# echo.net
KiCad netlist of a schematic drawn in EAGLE
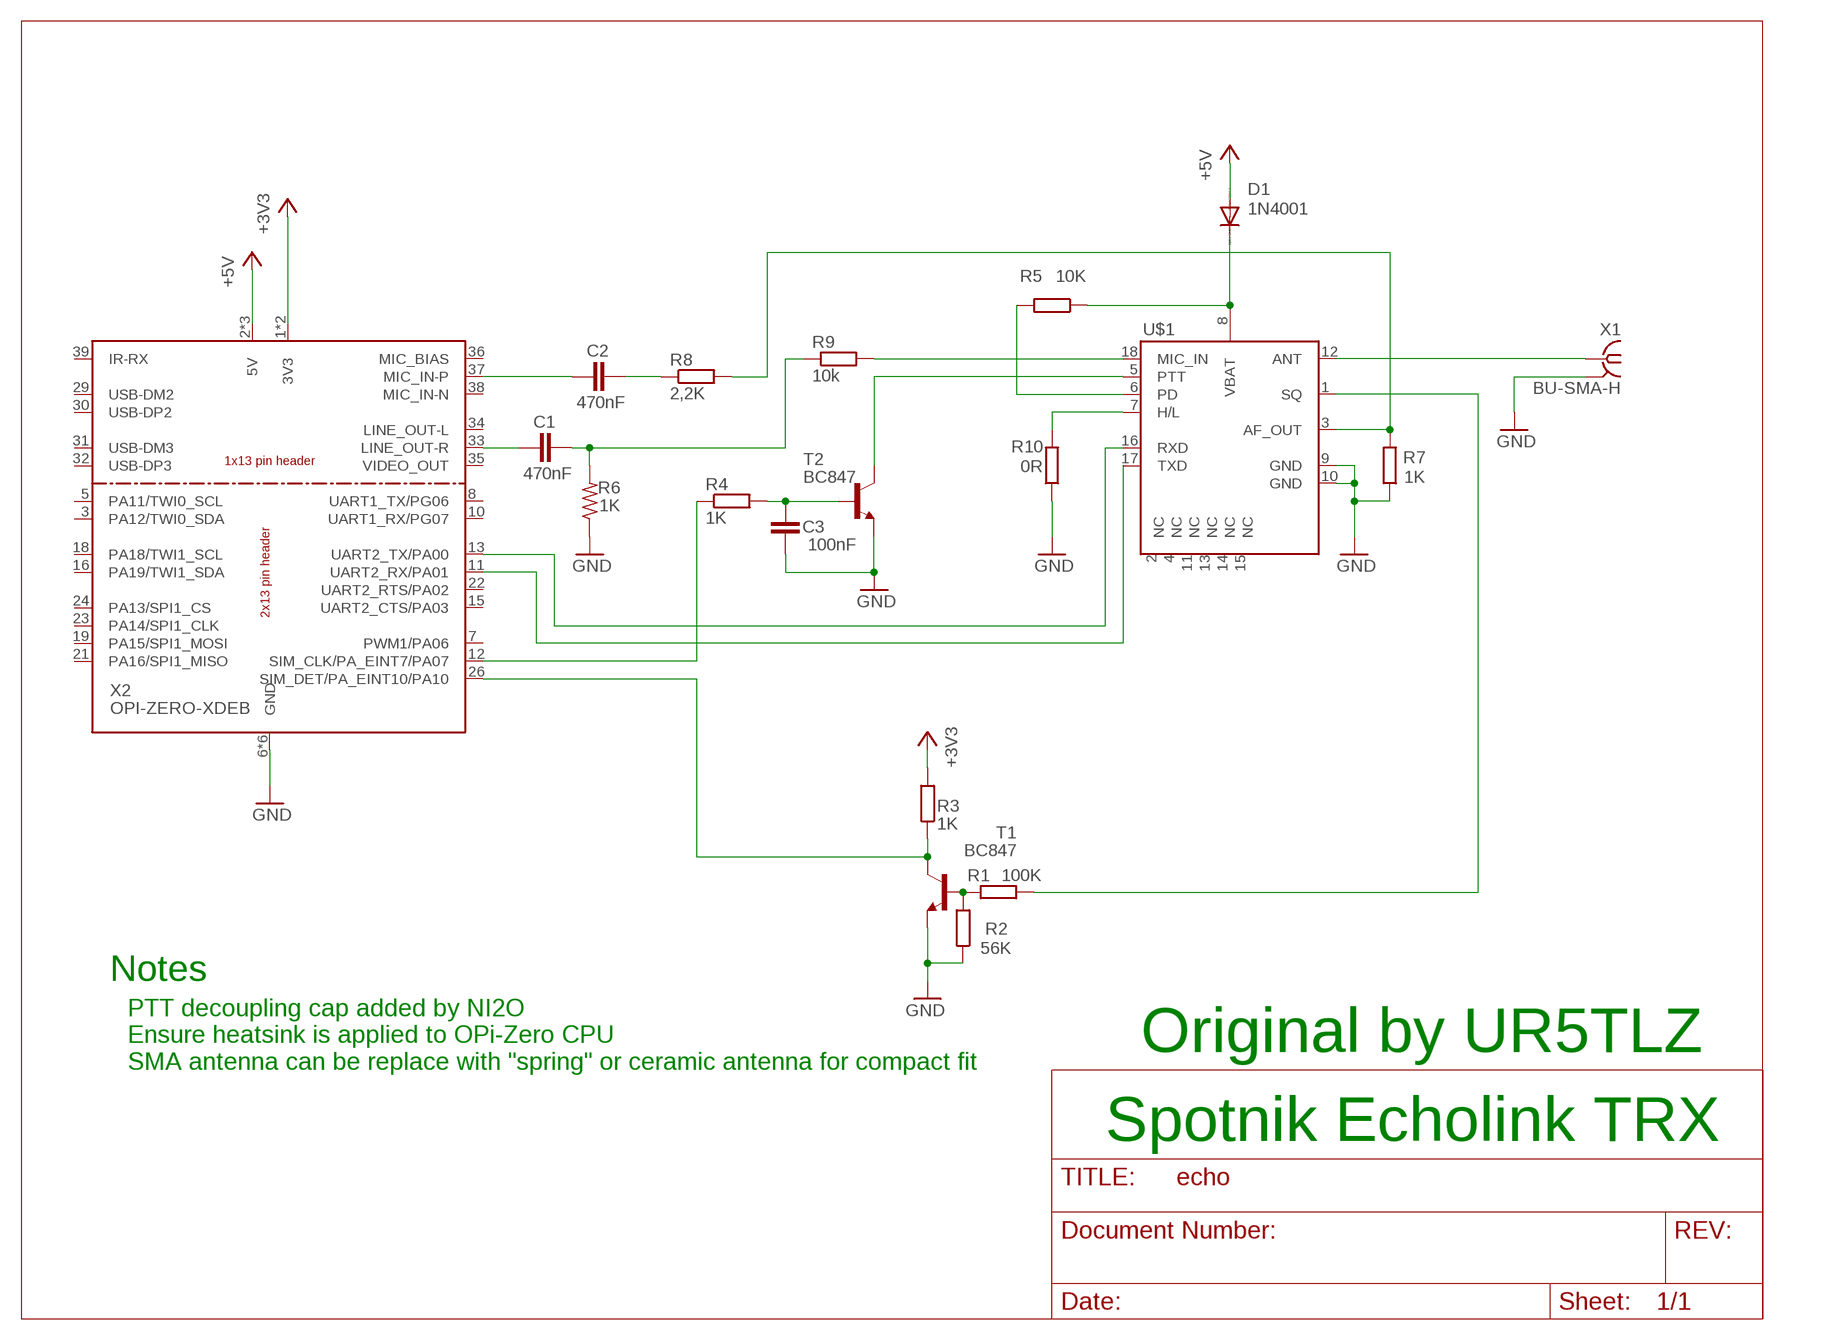
[diagram p0: schematic, sheet 1]

(export (version "E")
  (design (tool "Eeschema 10.0.6"))
  (components
    (comp (ref "C1")
      (value "470nF")
      (footprint "eagle-import:C0805")
      (libsource (lib "eagle-import") (part "C-EUC0805"))
    )
    (comp (ref "C2")
      (value "470nF")
      (footprint "eagle-import:C0805")
      (libsource (lib "eagle-import") (part "C-EUC0805"))
    )
    (comp (ref "C3")
      (value "100nF")
      (footprint "eagle-import:C0805")
      (libsource (lib "eagle-import") (part "C-EUC0805"))
    )
    (comp (ref "D1")
      (value "1N4001")
      (footprint "eagle-import:DO41-10")
      (libsource (lib "eagle-import") (part "DIODE-DO41-10"))
    )
    (comp (ref "R1")
      (value "100K")
      (footprint "eagle-import:R0805")
      (libsource (lib "eagle-import") (part "R-EU_R0805"))
    )
    (comp (ref "R2")
      (value "56K")
      (footprint "eagle-import:R0805")
      (libsource (lib "eagle-import") (part "R-EU_R0805"))
    )
    (comp (ref "R3")
      (value "1K")
      (footprint "eagle-import:R0805")
      (libsource (lib "eagle-import") (part "R-EU_R0805"))
    )
    (comp (ref "R4")
      (value "1K")
      (footprint "eagle-import:R0805")
      (libsource (lib "eagle-import") (part "R-EU_R0805"))
    )
    (comp (ref "R5")
      (value "10K")
      (footprint "eagle-import:R0805")
      (libsource (lib "eagle-import") (part "R-EU_R0805"))
    )
    (comp (ref "R6")
      (value "1K")
      (footprint "eagle-import:R0805")
      (libsource (lib "eagle-import") (part "R-US_R0805"))
    )
    (comp (ref "R7")
      (value "1K")
      (footprint "eagle-import:R0805")
      (libsource (lib "eagle-import") (part "R-EU_R0805"))
    )
    (comp (ref "R8")
      (value "2,2K")
      (footprint "eagle-import:R0805")
      (libsource (lib "eagle-import") (part "R-EU_R0805"))
    )
    (comp (ref "R9")
      (value "10k")
      (footprint "eagle-import:R0805")
      (libsource (lib "eagle-import") (part "R-EU_R0805"))
    )
    (comp (ref "R10")
      (value "0R")
      (footprint "eagle-import:R0805")
      (libsource (lib "eagle-import") (part "R-EU_R0805"))
    )
    (comp (ref "T1")
      (value "BC847")
      (footprint "eagle-import:SOT23")
      (libsource (lib "eagle-import") (part "BC847"))
    )
    (comp (ref "T2")
      (value "BC847")
      (footprint "eagle-import:SOT23")
      (libsource (lib "eagle-import") (part "BC847"))
    )
    (comp (ref "U$1")
      (value "DRA818A")
      (footprint "eagle-import:DRA818A")
      (libsource (lib "eagle-import") (part "DRA818A"))
    )
    (comp (ref "X1")
      (value "BU-SMA-H")
      (footprint "eagle-import:BU-SMA-H")
      (libsource (lib "eagle-import") (part "BU-SMA-H"))
    )
    (comp (ref "X2")
      (value "OPI-ZERO-XDEB")
      (footprint "eagle-import:OPIOHATDEB")
      (libsource (lib "eagle-import") (part "OPI-ZERO-XDEB"))
    )
  )
  (nets
    (net (code "1") (name "+3V3") (class "Default")
      (node (ref "R3") (pin "2") (pinfunction "2_2") (pintype "passive"))
      (node (ref "X2") (pin "1") (pinfunction "3V3_1") (pintype "power_in"))
      (node (ref "X2") (pin "17") (pinfunction "3V3_17") (pintype "power_in"))
    )
    (net (code "2") (name "+5V") (class "Default")
      (node (ref "D1") (pin "A") (pinfunction "A_A") (pintype "passive"))
      (node (ref "X2") (pin "2") (pinfunction "5V_2") (pintype "power_in"))
      (node (ref "X2") (pin "27") (pinfunction "5V_27") (pintype "power_in"))
      (node (ref "X2") (pin "4") (pinfunction "5V_4") (pintype "power_in"))
    )
    (net (code "3") (name "GND") (class "Default")
      (node (ref "C3") (pin "2") (pinfunction "2_2") (pintype "passive"))
      (node (ref "R10") (pin "1") (pinfunction "1_1") (pintype "passive"))
      (node (ref "R2") (pin "1") (pinfunction "1_1") (pintype "passive"))
      (node (ref "R6") (pin "1") (pinfunction "1_1") (pintype "passive"))
      (node (ref "R7") (pin "1") (pinfunction "1_1") (pintype "passive"))
      (node (ref "T1") (pin "2") (pinfunction "E_2") (pintype "passive"))
      (node (ref "T2") (pin "2") (pinfunction "E_2") (pintype "passive"))
      (node (ref "U$1") (pin "10") (pinfunction "GND_10") (pintype "bidirectional"))
      (node (ref "U$1") (pin "9") (pinfunction "GND_9") (pintype "bidirectional"))
      (node (ref "X1") (pin "2") (pinfunction "2_2") (pintype "passive"))
      (node (ref "X1") (pin "3") (pinfunction "2_3") (pintype "passive"))
      (node (ref "X1") (pin "4") (pinfunction "2_4") (pintype "passive"))
      (node (ref "X1") (pin "5") (pinfunction "2_5") (pintype "passive"))
      (node (ref "X2") (pin "14") (pinfunction "GND_14") (pintype "power_in"))
      (node (ref "X2") (pin "20") (pinfunction "GND_20") (pintype "power_in"))
      (node (ref "X2") (pin "25") (pinfunction "GND_25") (pintype "power_in"))
      (node (ref "X2") (pin "28") (pinfunction "GND_28") (pintype "power_in"))
      (node (ref "X2") (pin "6") (pinfunction "GND_6") (pintype "power_in"))
      (node (ref "X2") (pin "9") (pinfunction "GND_9") (pintype "power_in"))
    )
    (net (code "4") (name "Net-(C1-Pad1)") (class "Default")
      (node (ref "C1") (pin "1") (pinfunction "1_1") (pintype "passive"))
      (node (ref "R6") (pin "2") (pinfunction "2_2") (pintype "passive"))
      (node (ref "R9") (pin "1") (pinfunction "1_1") (pintype "passive"))
    )
    (net (code "5") (name "Net-(C2-Pad1)") (class "Default")
      (node (ref "C2") (pin "1") (pinfunction "1_1") (pintype "passive"))
      (node (ref "R8") (pin "1") (pinfunction "1_1") (pintype "passive"))
    )
    (net (code "6") (name "Net-(T1-B)") (class "Default")
      (node (ref "R1") (pin "2") (pinfunction "2_2") (pintype "passive"))
      (node (ref "R2") (pin "2") (pinfunction "2_2") (pintype "passive"))
      (node (ref "T1") (pin "1") (pinfunction "B_1") (pintype "passive"))
    )
    (net (code "7") (name "Net-(T1-C)") (class "Default")
      (node (ref "R3") (pin "1") (pinfunction "1_1") (pintype "passive"))
      (node (ref "T1") (pin "3") (pinfunction "C_3") (pintype "passive"))
      (node (ref "X2") (pin "26") (pinfunction "SIM_DET/PA_EINT10/PA10_26") (pintype "bidirectional"))
    )
    (net (code "8") (name "Net-(T2-B)") (class "Default")
      (node (ref "C3") (pin "1") (pinfunction "1_1") (pintype "passive"))
      (node (ref "R4") (pin "2") (pinfunction "2_2") (pintype "passive"))
      (node (ref "T2") (pin "1") (pinfunction "B_1") (pintype "passive"))
    )
    (net (code "9") (name "Net-(T2-C)") (class "Default")
      (node (ref "T2") (pin "3") (pinfunction "C_3") (pintype "passive"))
      (node (ref "U$1") (pin "5") (pinfunction "PTT_5") (pintype "bidirectional"))
    )
    (net (code "10") (name "Net-(U$1-AF_OUT)") (class "Default")
      (node (ref "R7") (pin "2") (pinfunction "2_2") (pintype "passive"))
      (node (ref "R8") (pin "2") (pinfunction "2_2") (pintype "passive"))
      (node (ref "U$1") (pin "3") (pinfunction "AF_OUT_3") (pintype "bidirectional"))
    )
    (net (code "11") (name "Net-(U$1-ANT)") (class "Default")
      (node (ref "U$1") (pin "12") (pinfunction "ANT_12") (pintype "bidirectional"))
      (node (ref "X1") (pin "1") (pinfunction "1_1") (pintype "passive"))
    )
    (net (code "12") (name "Net-(U$1-H{slash}L)") (class "Default")
      (node (ref "R10") (pin "2") (pinfunction "2_2") (pintype "passive"))
      (node (ref "U$1") (pin "7") (pinfunction "H/L_7") (pintype "bidirectional"))
    )
    (net (code "13") (name "Net-(U$1-MIC_IN)") (class "Default")
      (node (ref "R9") (pin "2") (pinfunction "2_2") (pintype "passive"))
      (node (ref "U$1") (pin "18") (pinfunction "MIC_IN_18") (pintype "bidirectional"))
    )
    (net (code "14") (name "Net-(U$1-PD)") (class "Default")
      (node (ref "R5") (pin "2") (pinfunction "2_2") (pintype "passive"))
      (node (ref "U$1") (pin "6") (pinfunction "PD_6") (pintype "bidirectional"))
    )
    (net (code "15") (name "Net-(U$1-RXD)") (class "Default")
      (node (ref "U$1") (pin "16") (pinfunction "RXD_16") (pintype "bidirectional"))
      (node (ref "X2") (pin "13") (pinfunction "UART2_TX/PA00_13") (pintype "bidirectional"))
    )
    (net (code "16") (name "Net-(U$1-SQ)") (class "Default")
      (node (ref "R1") (pin "1") (pinfunction "1_1") (pintype "passive"))
      (node (ref "U$1") (pin "1") (pinfunction "SQ_1") (pintype "bidirectional"))
    )
    (net (code "17") (name "Net-(U$1-TXD)") (class "Default")
      (node (ref "U$1") (pin "17") (pinfunction "TXD_17") (pintype "bidirectional"))
      (node (ref "X2") (pin "11") (pinfunction "UART2_RX/PA01_11") (pintype "bidirectional"))
    )
    (net (code "18") (name "Net-(U$1-VBAT)") (class "Default")
      (node (ref "D1") (pin "C") (pinfunction "C_C") (pintype "passive"))
      (node (ref "R5") (pin "1") (pinfunction "1_1") (pintype "passive"))
      (node (ref "U$1") (pin "8") (pinfunction "VBAT_8") (pintype "bidirectional"))
    )
    (net (code "19") (name "Net-(X2-LINE_OUT-R)") (class "Default")
      (node (ref "C1") (pin "2") (pinfunction "2_2") (pintype "passive"))
      (node (ref "X2") (pin "33") (pinfunction "LINE_OUT-R_33") (pintype "passive"))
    )
    (net (code "20") (name "Net-(X2-MIC_IN-P)") (class "Default")
      (node (ref "C2") (pin "2") (pinfunction "2_2") (pintype "passive"))
      (node (ref "X2") (pin "37") (pinfunction "MIC_IN-P_37") (pintype "passive"))
    )
    (net (code "21") (name "Net-(X2-SIM_CLK{slash}PA_EINT7{slash}PA07)") (class "Default")
      (node (ref "R4") (pin "1") (pinfunction "1_1") (pintype "passive"))
      (node (ref "X2") (pin "12") (pinfunction "SIM_CLK/PA_EINT7/PA07_12") (pintype "bidirectional"))
    )
    (net (code "22") (name "unconnected-(U$1-NC-Pad2)") (class "Default")
      (node (ref "U$1") (pin "2") (pinfunction "NC_2") (pintype "bidirectional"))
    )
    (net (code "23") (name "unconnected-(U$1-NC-Pad4)") (class "Default")
      (node (ref "U$1") (pin "4") (pinfunction "NC_4") (pintype "bidirectional"))
    )
    (net (code "24") (name "unconnected-(U$1-NC-Pad11)") (class "Default")
      (node (ref "U$1") (pin "11") (pinfunction "NC_11") (pintype "bidirectional"))
    )
    (net (code "25") (name "unconnected-(U$1-NC-Pad13)") (class "Default")
      (node (ref "U$1") (pin "13") (pinfunction "NC_13") (pintype "bidirectional"))
    )
    (net (code "26") (name "unconnected-(U$1-NC-Pad14)") (class "Default")
      (node (ref "U$1") (pin "14") (pinfunction "NC_14") (pintype "bidirectional"))
    )
    (net (code "27") (name "unconnected-(U$1-NC-Pad15)") (class "Default")
      (node (ref "U$1") (pin "15") (pinfunction "NC_15") (pintype "bidirectional"))
    )
    (net (code "28") (name "unconnected-(X2-IR-RX-Pad39)") (class "Default")
      (node (ref "X2") (pin "39") (pinfunction "IR-RX_39") (pintype "passive"))
    )
    (net (code "29") (name "unconnected-(X2-LINE_OUT-L-Pad34)") (class "Default")
      (node (ref "X2") (pin "34") (pinfunction "LINE_OUT-L_34") (pintype "passive"))
    )
    (net (code "30") (name "unconnected-(X2-MIC_BIAS-Pad36)") (class "Default")
      (node (ref "X2") (pin "36") (pinfunction "MIC_BIAS_36") (pintype "passive"))
    )
    (net (code "31") (name "unconnected-(X2-MIC_IN-N-Pad38)") (class "Default")
      (node (ref "X2") (pin "38") (pinfunction "MIC_IN-N_38") (pintype "passive"))
    )
    (net (code "32") (name "unconnected-(X2-PA11{slash}TWI0_SCL-Pad5)") (class "Default")
      (node (ref "X2") (pin "5") (pinfunction "PA11/TWI0_SCL_5") (pintype "bidirectional"))
    )
    (net (code "33") (name "unconnected-(X2-PA12{slash}TWI0_SDA-Pad3)") (class "Default")
      (node (ref "X2") (pin "3") (pinfunction "PA12/TWI0_SDA_3") (pintype "bidirectional"))
    )
    (net (code "34") (name "unconnected-(X2-PA13{slash}SPI1_CS-Pad24)") (class "Default")
      (node (ref "X2") (pin "24") (pinfunction "PA13/SPI1_CS_24") (pintype "bidirectional"))
    )
    (net (code "35") (name "unconnected-(X2-PA14{slash}SPI1_CLK-Pad23)") (class "Default")
      (node (ref "X2") (pin "23") (pinfunction "PA14/SPI1_CLK_23") (pintype "bidirectional"))
    )
    (net (code "36") (name "unconnected-(X2-PA15{slash}SPI1_MOSI-Pad19)") (class "Default")
      (node (ref "X2") (pin "19") (pinfunction "PA15/SPI1_MOSI_19") (pintype "bidirectional"))
    )
    (net (code "37") (name "unconnected-(X2-PA16{slash}SPI1_MISO-Pad21)") (class "Default")
      (node (ref "X2") (pin "21") (pinfunction "PA16/SPI1_MISO_21") (pintype "bidirectional"))
    )
    (net (code "38") (name "unconnected-(X2-PA18{slash}TWI1_SCL-Pad18)") (class "Default")
      (node (ref "X2") (pin "18") (pinfunction "PA18/TWI1_SCL_18") (pintype "bidirectional"))
    )
    (net (code "39") (name "unconnected-(X2-PA19{slash}TWI1_SDA-Pad16)") (class "Default")
      (node (ref "X2") (pin "16") (pinfunction "PA19/TWI1_SDA_16") (pintype "bidirectional"))
    )
    (net (code "40") (name "unconnected-(X2-PWM1{slash}PA06-Pad7)") (class "Default")
      (node (ref "X2") (pin "7") (pinfunction "PWM1/PA06_7") (pintype "bidirectional"))
    )
    (net (code "41") (name "unconnected-(X2-UART1_RX{slash}PG07-Pad10)") (class "Default")
      (node (ref "X2") (pin "10") (pinfunction "UART1_RX/PG07_10") (pintype "bidirectional"))
    )
    (net (code "42") (name "unconnected-(X2-UART1_TX{slash}PG06-Pad8)") (class "Default")
      (node (ref "X2") (pin "8") (pinfunction "UART1_TX/PG06_8") (pintype "bidirectional"))
    )
    (net (code "43") (name "unconnected-(X2-UART2_CTS{slash}PA03-Pad15)") (class "Default")
      (node (ref "X2") (pin "15") (pinfunction "UART2_CTS/PA03_15") (pintype "bidirectional"))
    )
    (net (code "44") (name "unconnected-(X2-UART2_RTS{slash}PA02-Pad22)") (class "Default")
      (node (ref "X2") (pin "22") (pinfunction "UART2_RTS/PA02_22") (pintype "bidirectional"))
    )
    (net (code "45") (name "unconnected-(X2-USB-DM2-Pad29)") (class "Default")
      (node (ref "X2") (pin "29") (pinfunction "USB-DM2_29") (pintype "bidirectional"))
    )
    (net (code "46") (name "unconnected-(X2-USB-DM3-Pad31)") (class "Default")
      (node (ref "X2") (pin "31") (pinfunction "USB-DM3_31") (pintype "bidirectional"))
    )
    (net (code "47") (name "unconnected-(X2-USB-DP2-Pad30)") (class "Default")
      (node (ref "X2") (pin "30") (pinfunction "USB-DP2_30") (pintype "bidirectional"))
    )
    (net (code "48") (name "unconnected-(X2-USB-DP3-Pad32)") (class "Default")
      (node (ref "X2") (pin "32") (pinfunction "USB-DP3_32") (pintype "bidirectional"))
    )
    (net (code "49") (name "unconnected-(X2-VIDEO_OUT-Pad35)") (class "Default")
      (node (ref "X2") (pin "35") (pinfunction "VIDEO_OUT_35") (pintype "passive"))
    )
  )
)
